# EIB36-JAE_FB-Av1.net
KiCad netlist of a schematic drawn in EAGLE
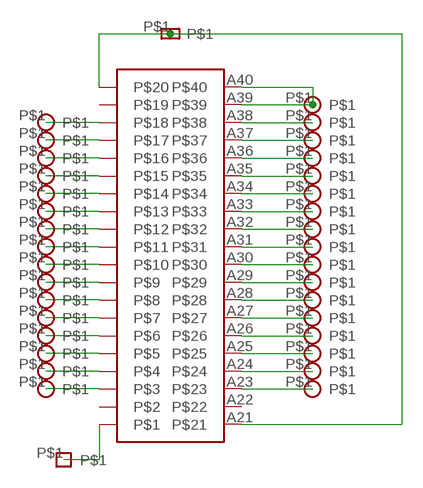
[diagram p0: schematic, sheet 1]

(export (version "E")
  (design (tool "Eeschema 10.0.6"))
  (components
    (comp (ref "U$1")
      (value "WR-40SB-VFH30")
      (footprint "eagle-import:WR-40SB-VFH30")
      (libsource (lib "eagle-import") (part "WR-40SB-VFH30"))
    )
    (comp (ref "U$2")
      (value "EIB-GND-HOLE-PAD-SMALL")
      (footprint "eagle-import:EIB-GND-HOLE-PAD-SMALL")
      (libsource (lib "eagle-import") (part "EIB-GND-HOLE-PAD-SMALL"))
    )
    (comp (ref "U$3")
      (value "EIB-GND-HOLE-PAD")
      (footprint "eagle-import:EIB-GND-HOLE-PAD")
      (libsource (lib "eagle-import") (part "EIB-GND-HOLE-PAD"))
    )
    (comp (ref "U$5")
      (value "EIB-TETRODE-HOLE-PAD")
      (footprint "eagle-import:EIB-TETRODE-HOLE-PAD")
      (libsource (lib "eagle-import") (part "EIB-TETRODE-HOLE-PAD"))
    )
    (comp (ref "U$6")
      (value "EIB-TETRODE-HOLE-PAD")
      (footprint "eagle-import:EIB-TETRODE-HOLE-PAD")
      (libsource (lib "eagle-import") (part "EIB-TETRODE-HOLE-PAD"))
    )
    (comp (ref "U$7")
      (value "EIB-TETRODE-HOLE-PAD")
      (footprint "eagle-import:EIB-TETRODE-HOLE-PAD")
      (libsource (lib "eagle-import") (part "EIB-TETRODE-HOLE-PAD"))
    )
    (comp (ref "U$8")
      (value "EIB-TETRODE-HOLE-PAD")
      (footprint "eagle-import:EIB-TETRODE-HOLE-PAD")
      (libsource (lib "eagle-import") (part "EIB-TETRODE-HOLE-PAD"))
    )
    (comp (ref "U$9")
      (value "EIB-TETRODE-HOLE-PAD")
      (footprint "eagle-import:EIB-TETRODE-HOLE-PAD")
      (libsource (lib "eagle-import") (part "EIB-TETRODE-HOLE-PAD"))
    )
    (comp (ref "U$10")
      (value "EIB-TETRODE-HOLE-PAD")
      (footprint "eagle-import:EIB-TETRODE-HOLE-PAD")
      (libsource (lib "eagle-import") (part "EIB-TETRODE-HOLE-PAD"))
    )
    (comp (ref "U$11")
      (value "EIB-TETRODE-HOLE-PAD")
      (footprint "eagle-import:EIB-TETRODE-HOLE-PAD")
      (libsource (lib "eagle-import") (part "EIB-TETRODE-HOLE-PAD"))
    )
    (comp (ref "U$12")
      (value "EIB-TETRODE-HOLE-PAD")
      (footprint "eagle-import:EIB-TETRODE-HOLE-PAD")
      (libsource (lib "eagle-import") (part "EIB-TETRODE-HOLE-PAD"))
    )
    (comp (ref "U$13")
      (value "EIB-TETRODE-HOLE-PAD")
      (footprint "eagle-import:EIB-TETRODE-HOLE-PAD")
      (libsource (lib "eagle-import") (part "EIB-TETRODE-HOLE-PAD"))
    )
    (comp (ref "U$14")
      (value "EIB-TETRODE-HOLE-PAD")
      (footprint "eagle-import:EIB-TETRODE-HOLE-PAD")
      (libsource (lib "eagle-import") (part "EIB-TETRODE-HOLE-PAD"))
    )
    (comp (ref "U$15")
      (value "EIB-TETRODE-HOLE-PAD")
      (footprint "eagle-import:EIB-TETRODE-HOLE-PAD")
      (libsource (lib "eagle-import") (part "EIB-TETRODE-HOLE-PAD"))
    )
    (comp (ref "U$16")
      (value "EIB-TETRODE-HOLE-PAD")
      (footprint "eagle-import:EIB-TETRODE-HOLE-PAD")
      (libsource (lib "eagle-import") (part "EIB-TETRODE-HOLE-PAD"))
    )
    (comp (ref "U$17")
      (value "EIB-TETRODE-HOLE-PAD")
      (footprint "eagle-import:EIB-TETRODE-HOLE-PAD")
      (libsource (lib "eagle-import") (part "EIB-TETRODE-HOLE-PAD"))
    )
    (comp (ref "U$18")
      (value "EIB-TETRODE-HOLE-PAD")
      (footprint "eagle-import:EIB-TETRODE-HOLE-PAD")
      (libsource (lib "eagle-import") (part "EIB-TETRODE-HOLE-PAD"))
    )
    (comp (ref "U$19")
      (value "EIB-TETRODE-HOLE-PAD")
      (footprint "eagle-import:EIB-TETRODE-HOLE-PAD")
      (libsource (lib "eagle-import") (part "EIB-TETRODE-HOLE-PAD"))
    )
    (comp (ref "U$20")
      (value "EIB-TETRODE-HOLE-PAD")
      (footprint "eagle-import:EIB-TETRODE-HOLE-PAD")
      (libsource (lib "eagle-import") (part "EIB-TETRODE-HOLE-PAD"))
    )
    (comp (ref "U$22")
      (value "EIB-TETRODE-HOLE-PAD")
      (footprint "eagle-import:EIB-TETRODE-HOLE-PAD")
      (libsource (lib "eagle-import") (part "EIB-TETRODE-HOLE-PAD"))
    )
    (comp (ref "U$23")
      (value "EIB-TETRODE-HOLE-PAD")
      (footprint "eagle-import:EIB-TETRODE-HOLE-PAD")
      (libsource (lib "eagle-import") (part "EIB-TETRODE-HOLE-PAD"))
    )
    (comp (ref "U$24")
      (value "EIB-TETRODE-HOLE-PAD")
      (footprint "eagle-import:EIB-TETRODE-HOLE-PAD")
      (libsource (lib "eagle-import") (part "EIB-TETRODE-HOLE-PAD"))
    )
    (comp (ref "U$25")
      (value "EIB-TETRODE-HOLE-PAD")
      (footprint "eagle-import:EIB-TETRODE-HOLE-PAD")
      (libsource (lib "eagle-import") (part "EIB-TETRODE-HOLE-PAD"))
    )
    (comp (ref "U$26")
      (value "EIB-TETRODE-HOLE-PAD")
      (footprint "eagle-import:EIB-TETRODE-HOLE-PAD")
      (libsource (lib "eagle-import") (part "EIB-TETRODE-HOLE-PAD"))
    )
    (comp (ref "U$27")
      (value "EIB-TETRODE-HOLE-PAD")
      (footprint "eagle-import:EIB-TETRODE-HOLE-PAD")
      (libsource (lib "eagle-import") (part "EIB-TETRODE-HOLE-PAD"))
    )
    (comp (ref "U$28")
      (value "EIB-TETRODE-HOLE-PAD")
      (footprint "eagle-import:EIB-TETRODE-HOLE-PAD")
      (libsource (lib "eagle-import") (part "EIB-TETRODE-HOLE-PAD"))
    )
    (comp (ref "U$29")
      (value "EIB-TETRODE-HOLE-PAD")
      (footprint "eagle-import:EIB-TETRODE-HOLE-PAD")
      (libsource (lib "eagle-import") (part "EIB-TETRODE-HOLE-PAD"))
    )
    (comp (ref "U$30")
      (value "EIB-TETRODE-HOLE-PAD")
      (footprint "eagle-import:EIB-TETRODE-HOLE-PAD")
      (libsource (lib "eagle-import") (part "EIB-TETRODE-HOLE-PAD"))
    )
    (comp (ref "U$31")
      (value "EIB-TETRODE-HOLE-PAD")
      (footprint "eagle-import:EIB-TETRODE-HOLE-PAD")
      (libsource (lib "eagle-import") (part "EIB-TETRODE-HOLE-PAD"))
    )
    (comp (ref "U$32")
      (value "EIB-TETRODE-HOLE-PAD")
      (footprint "eagle-import:EIB-TETRODE-HOLE-PAD")
      (libsource (lib "eagle-import") (part "EIB-TETRODE-HOLE-PAD"))
    )
    (comp (ref "U$33")
      (value "EIB-TETRODE-HOLE-PAD")
      (footprint "eagle-import:EIB-TETRODE-HOLE-PAD")
      (libsource (lib "eagle-import") (part "EIB-TETRODE-HOLE-PAD"))
    )
    (comp (ref "U$34")
      (value "EIB-TETRODE-HOLE-PAD")
      (footprint "eagle-import:EIB-TETRODE-HOLE-PAD")
      (libsource (lib "eagle-import") (part "EIB-TETRODE-HOLE-PAD"))
    )
    (comp (ref "U$35")
      (value "EIB-TETRODE-HOLE-PAD")
      (footprint "eagle-import:EIB-TETRODE-HOLE-PAD")
      (libsource (lib "eagle-import") (part "EIB-TETRODE-HOLE-PAD"))
    )
    (comp (ref "U$36")
      (value "EIB-TETRODE-HOLE-PAD")
      (footprint "eagle-import:EIB-TETRODE-HOLE-PAD")
      (libsource (lib "eagle-import") (part "EIB-TETRODE-HOLE-PAD"))
    )
    (comp (ref "U$37")
      (value "EIB-TETRODE-HOLE-PAD")
      (footprint "eagle-import:EIB-TETRODE-HOLE-PAD")
      (libsource (lib "eagle-import") (part "EIB-TETRODE-HOLE-PAD"))
    )
    (comp (ref "U$38")
      (value "EIB-TETRODE-HOLE-PAD")
      (footprint "eagle-import:EIB-TETRODE-HOLE-PAD")
      (libsource (lib "eagle-import") (part "EIB-TETRODE-HOLE-PAD"))
    )
  )
  (nets
    (net (code "1") (name "Net-(U$1-P$1)") (class "Default")
      (node (ref "U$1") (pin "A1") (pinfunction "P$1_A1") (pintype "bidirectional"))
      (node (ref "U$3") (pin "P$1") (pinfunction "P$1_P$1") (pintype "bidirectional"))
    )
    (net (code "2") (name "Net-(U$1-P$3)") (class "Default")
      (node (ref "U$1") (pin "A3") (pinfunction "P$3_A3") (pintype "bidirectional"))
      (node (ref "U$20") (pin "P$1") (pinfunction "P$1_P$1") (pintype "bidirectional"))
    )
    (net (code "3") (name "Net-(U$1-P$4)") (class "Default")
      (node (ref "U$1") (pin "A4") (pinfunction "P$4_A4") (pintype "bidirectional"))
      (node (ref "U$19") (pin "P$1") (pinfunction "P$1_P$1") (pintype "bidirectional"))
    )
    (net (code "4") (name "Net-(U$1-P$5)") (class "Default")
      (node (ref "U$1") (pin "A5") (pinfunction "P$5_A5") (pintype "bidirectional"))
      (node (ref "U$18") (pin "P$1") (pinfunction "P$1_P$1") (pintype "bidirectional"))
    )
    (net (code "5") (name "Net-(U$1-P$6)") (class "Default")
      (node (ref "U$1") (pin "A6") (pinfunction "P$6_A6") (pintype "bidirectional"))
      (node (ref "U$17") (pin "P$1") (pinfunction "P$1_P$1") (pintype "bidirectional"))
    )
    (net (code "6") (name "Net-(U$1-P$7)") (class "Default")
      (node (ref "U$1") (pin "A7") (pinfunction "P$7_A7") (pintype "bidirectional"))
      (node (ref "U$16") (pin "P$1") (pinfunction "P$1_P$1") (pintype "bidirectional"))
    )
    (net (code "7") (name "Net-(U$1-P$8)") (class "Default")
      (node (ref "U$1") (pin "A8") (pinfunction "P$8_A8") (pintype "bidirectional"))
      (node (ref "U$15") (pin "P$1") (pinfunction "P$1_P$1") (pintype "bidirectional"))
    )
    (net (code "8") (name "Net-(U$1-P$9)") (class "Default")
      (node (ref "U$1") (pin "A9") (pinfunction "P$9_A9") (pintype "bidirectional"))
      (node (ref "U$14") (pin "P$1") (pinfunction "P$1_P$1") (pintype "bidirectional"))
    )
    (net (code "9") (name "Net-(U$1-P$10)") (class "Default")
      (node (ref "U$1") (pin "A10") (pinfunction "P$10_A10") (pintype "bidirectional"))
      (node (ref "U$13") (pin "P$1") (pinfunction "P$1_P$1") (pintype "bidirectional"))
    )
    (net (code "10") (name "Net-(U$1-P$11)") (class "Default")
      (node (ref "U$1") (pin "A11") (pinfunction "P$11_A11") (pintype "bidirectional"))
      (node (ref "U$12") (pin "P$1") (pinfunction "P$1_P$1") (pintype "bidirectional"))
    )
    (net (code "11") (name "Net-(U$1-P$12)") (class "Default")
      (node (ref "U$1") (pin "A12") (pinfunction "P$12_A12") (pintype "bidirectional"))
      (node (ref "U$11") (pin "P$1") (pinfunction "P$1_P$1") (pintype "bidirectional"))
    )
    (net (code "12") (name "Net-(U$1-P$13)") (class "Default")
      (node (ref "U$1") (pin "A13") (pinfunction "P$13_A13") (pintype "bidirectional"))
      (node (ref "U$10") (pin "P$1") (pinfunction "P$1_P$1") (pintype "bidirectional"))
    )
    (net (code "13") (name "Net-(U$1-P$14)") (class "Default")
      (node (ref "U$1") (pin "A14") (pinfunction "P$14_A14") (pintype "bidirectional"))
      (node (ref "U$9") (pin "P$1") (pinfunction "P$1_P$1") (pintype "bidirectional"))
    )
    (net (code "14") (name "Net-(U$1-P$15)") (class "Default")
      (node (ref "U$1") (pin "A15") (pinfunction "P$15_A15") (pintype "bidirectional"))
      (node (ref "U$8") (pin "P$1") (pinfunction "P$1_P$1") (pintype "bidirectional"))
    )
    (net (code "15") (name "Net-(U$1-P$16)") (class "Default")
      (node (ref "U$1") (pin "A16") (pinfunction "P$16_A16") (pintype "bidirectional"))
      (node (ref "U$7") (pin "P$1") (pinfunction "P$1_P$1") (pintype "bidirectional"))
    )
    (net (code "16") (name "Net-(U$1-P$17)") (class "Default")
      (node (ref "U$1") (pin "A17") (pinfunction "P$17_A17") (pintype "bidirectional"))
      (node (ref "U$6") (pin "P$1") (pinfunction "P$1_P$1") (pintype "bidirectional"))
    )
    (net (code "17") (name "Net-(U$1-P$18)") (class "Default")
      (node (ref "U$1") (pin "A18") (pinfunction "P$18_A18") (pintype "bidirectional"))
      (node (ref "U$5") (pin "P$1") (pinfunction "P$1_P$1") (pintype "bidirectional"))
    )
    (net (code "18") (name "Net-(U$1-P$20)") (class "Default")
      (node (ref "U$1") (pin "A20") (pinfunction "P$20_A20") (pintype "bidirectional"))
      (node (ref "U$1") (pin "A21") (pinfunction "P$21_A21") (pintype "bidirectional"))
      (node (ref "U$2") (pin "P$1") (pinfunction "P$1_P$1") (pintype "bidirectional"))
    )
    (net (code "19") (name "Net-(U$1-P$23)") (class "Default")
      (node (ref "U$1") (pin "A23") (pinfunction "P$23_A23") (pintype "bidirectional"))
      (node (ref "U$38") (pin "P$1") (pinfunction "P$1_P$1") (pintype "bidirectional"))
    )
    (net (code "20") (name "Net-(U$1-P$24)") (class "Default")
      (node (ref "U$1") (pin "A24") (pinfunction "P$24_A24") (pintype "bidirectional"))
      (node (ref "U$37") (pin "P$1") (pinfunction "P$1_P$1") (pintype "bidirectional"))
    )
    (net (code "21") (name "Net-(U$1-P$25)") (class "Default")
      (node (ref "U$1") (pin "A25") (pinfunction "P$25_A25") (pintype "bidirectional"))
      (node (ref "U$36") (pin "P$1") (pinfunction "P$1_P$1") (pintype "bidirectional"))
    )
    (net (code "22") (name "Net-(U$1-P$26)") (class "Default")
      (node (ref "U$1") (pin "A26") (pinfunction "P$26_A26") (pintype "bidirectional"))
      (node (ref "U$35") (pin "P$1") (pinfunction "P$1_P$1") (pintype "bidirectional"))
    )
    (net (code "23") (name "Net-(U$1-P$27)") (class "Default")
      (node (ref "U$1") (pin "A27") (pinfunction "P$27_A27") (pintype "bidirectional"))
      (node (ref "U$34") (pin "P$1") (pinfunction "P$1_P$1") (pintype "bidirectional"))
    )
    (net (code "24") (name "Net-(U$1-P$28)") (class "Default")
      (node (ref "U$1") (pin "A28") (pinfunction "P$28_A28") (pintype "bidirectional"))
      (node (ref "U$33") (pin "P$1") (pinfunction "P$1_P$1") (pintype "bidirectional"))
    )
    (net (code "25") (name "Net-(U$1-P$29)") (class "Default")
      (node (ref "U$1") (pin "A29") (pinfunction "P$29_A29") (pintype "bidirectional"))
      (node (ref "U$32") (pin "P$1") (pinfunction "P$1_P$1") (pintype "bidirectional"))
    )
    (net (code "26") (name "Net-(U$1-P$30)") (class "Default")
      (node (ref "U$1") (pin "A30") (pinfunction "P$30_A30") (pintype "bidirectional"))
      (node (ref "U$31") (pin "P$1") (pinfunction "P$1_P$1") (pintype "bidirectional"))
    )
    (net (code "27") (name "Net-(U$1-P$31)") (class "Default")
      (node (ref "U$1") (pin "A31") (pinfunction "P$31_A31") (pintype "bidirectional"))
      (node (ref "U$30") (pin "P$1") (pinfunction "P$1_P$1") (pintype "bidirectional"))
    )
    (net (code "28") (name "Net-(U$1-P$32)") (class "Default")
      (node (ref "U$1") (pin "A32") (pinfunction "P$32_A32") (pintype "bidirectional"))
      (node (ref "U$29") (pin "P$1") (pinfunction "P$1_P$1") (pintype "bidirectional"))
    )
    (net (code "29") (name "Net-(U$1-P$33)") (class "Default")
      (node (ref "U$1") (pin "A33") (pinfunction "P$33_A33") (pintype "bidirectional"))
      (node (ref "U$28") (pin "P$1") (pinfunction "P$1_P$1") (pintype "bidirectional"))
    )
    (net (code "30") (name "Net-(U$1-P$34)") (class "Default")
      (node (ref "U$1") (pin "A34") (pinfunction "P$34_A34") (pintype "bidirectional"))
      (node (ref "U$27") (pin "P$1") (pinfunction "P$1_P$1") (pintype "bidirectional"))
    )
    (net (code "31") (name "Net-(U$1-P$35)") (class "Default")
      (node (ref "U$1") (pin "A35") (pinfunction "P$35_A35") (pintype "bidirectional"))
      (node (ref "U$26") (pin "P$1") (pinfunction "P$1_P$1") (pintype "bidirectional"))
    )
    (net (code "32") (name "Net-(U$1-P$36)") (class "Default")
      (node (ref "U$1") (pin "A36") (pinfunction "P$36_A36") (pintype "bidirectional"))
      (node (ref "U$25") (pin "P$1") (pinfunction "P$1_P$1") (pintype "bidirectional"))
    )
    (net (code "33") (name "Net-(U$1-P$37)") (class "Default")
      (node (ref "U$1") (pin "A37") (pinfunction "P$37_A37") (pintype "bidirectional"))
      (node (ref "U$24") (pin "P$1") (pinfunction "P$1_P$1") (pintype "bidirectional"))
    )
    (net (code "34") (name "Net-(U$1-P$38)") (class "Default")
      (node (ref "U$1") (pin "A38") (pinfunction "P$38_A38") (pintype "bidirectional"))
      (node (ref "U$23") (pin "P$1") (pinfunction "P$1_P$1") (pintype "bidirectional"))
    )
    (net (code "35") (name "Net-(U$1-P$39)") (class "Default")
      (node (ref "U$1") (pin "A39") (pinfunction "P$39_A39") (pintype "bidirectional"))
      (node (ref "U$1") (pin "A40") (pinfunction "P$40_A40") (pintype "bidirectional"))
      (node (ref "U$22") (pin "P$1") (pinfunction "P$1_P$1") (pintype "bidirectional"))
    )
    (net (code "36") (name "unconnected-(U$1-P$2-PadA2)") (class "Default")
      (node (ref "U$1") (pin "A2") (pinfunction "P$2_A2") (pintype "bidirectional"))
    )
    (net (code "37") (name "unconnected-(U$1-P$19-PadA19)") (class "Default")
      (node (ref "U$1") (pin "A19") (pinfunction "P$19_A19") (pintype "bidirectional"))
    )
    (net (code "38") (name "unconnected-(U$1-P$22-PadA22)") (class "Default")
      (node (ref "U$1") (pin "A22") (pinfunction "P$22_A22") (pintype "bidirectional"))
    )
  )
)
